# H_BRIDGE.net
KiCad netlist of a schematic drawn in Altium Designer
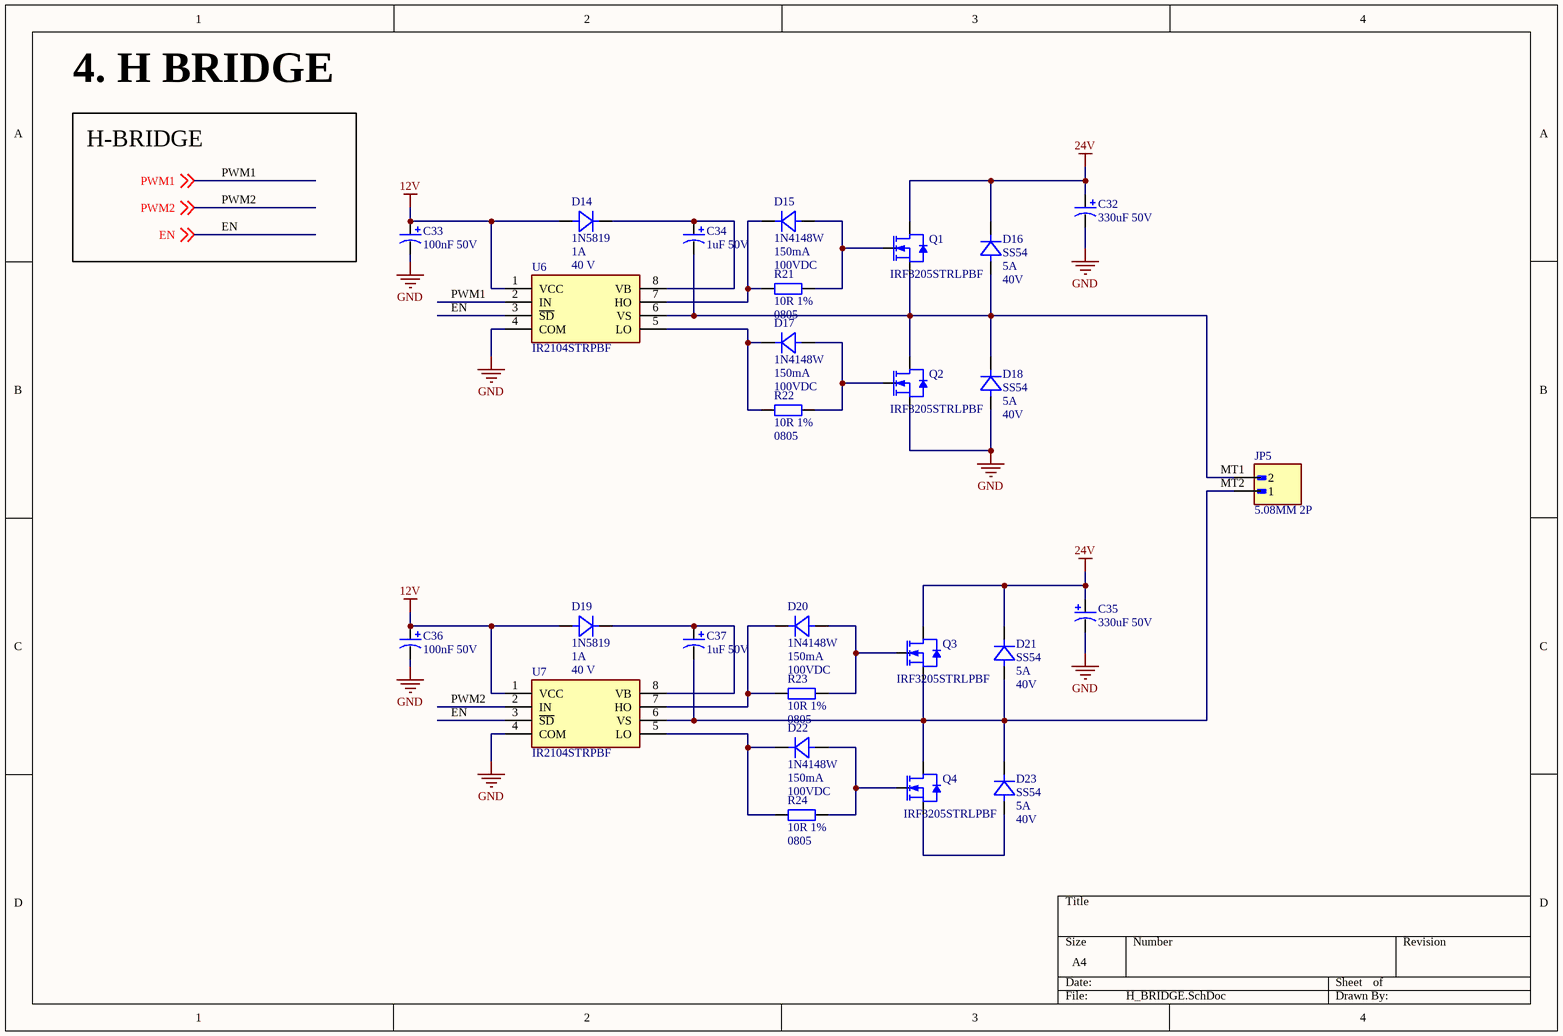
[diagram p0: H_BRIDGE.SchDoc]

(export (version "E")
  (design (tool "Eeschema 10.0.6"))
  (components
    (comp (ref "C32")
      (value "330uF 50V")
      (footprint "CAP-ALU-SMD-G-NEW")
      (description "330uF 50V 170mA@120Hz ±20% SMD,D10xL10.2mm Aluminum Electrolytic Capacitors - SMD ROHS")
      (fields
        (field (name "MANUFACTURER") "KNSCHA")
        (field (name "MANUFACTURE PART NUMBER") "RVT330UF50V167RV085")
      )
      (libsource (lib "Capacitors") (part "C_ALU_330uF_50V_G"))
    )
    (comp (ref "C33")
      (value "100nF 50V")
      (footprint "CAP-ALU-SMD-B -NEW")
      (description "100nF 50V ±20% SMD,D4xL5.4mm Aluminum Electrolytic Capacitors - SMD ROHS")
      (fields
        (field (name "MANUFACTURER") "Changzhou Huawei Elec")
        (field (name "MANUFACTURE PART NUMBER") "VT1H0R1MB054000CE0")
      )
      (libsource (lib "Capacitors") (part "C_ALU_100nF_50V_B"))
    )
    (comp (ref "C34")
      (value "1uF 50V")
      (footprint "CAP-ALU-SMD-B -NEW")
      (description "1uF 50V 7mA@120Hz ±20% SMD,D4xL5.4mm Aluminum Electrolytic Capacitors - SMD ROHS")
      (fields (field (name "MANUFACTURER") "KNSCHA") (field (name "MANUFACTURE PART NUMBER") "RST1UF50V017"))
      (libsource (lib "Capacitors") (part "C_ALU_1uF_50V_B"))
    )
    (comp (ref "C35")
      (value "330uF 50V")
      (footprint "CAP-ALU-SMD-G-NEW")
      (description "330uF 50V 170mA@120Hz ±20% SMD,D10xL10.2mm Aluminum Electrolytic Capacitors - SMD ROHS")
      (fields
        (field (name "MANUFACTURER") "KNSCHA")
        (field (name "MANUFACTURE PART NUMBER") "RVT330UF50V167RV085")
      )
      (libsource (lib "") (part "C_ALU_330uF_50V_G_1"))
    )
    (comp (ref "C36")
      (value "100nF 50V")
      (footprint "CAP-ALU-SMD-B -NEW")
      (description "100nF 50V ±20% SMD,D4xL5.4mm Aluminum Electrolytic Capacitors - SMD ROHS")
      (fields
        (field (name "MANUFACTURER") "Changzhou Huawei Elec")
        (field (name "MANUFACTURE PART NUMBER") "VT1H0R1MB054000CE0")
      )
      (libsource (lib "Capacitors") (part "C_ALU_100nF_50V_B"))
    )
    (comp (ref "C37")
      (value "1uF 50V")
      (footprint "CAP-ALU-SMD-B -NEW")
      (description "1uF 50V 7mA@120Hz ±20% SMD,D4xL5.4mm Aluminum Electrolytic Capacitors - SMD ROHS")
      (fields (field (name "MANUFACTURER") "KNSCHA") (field (name "MANUFACTURE PART NUMBER") "RST1UF50V017"))
      (libsource (lib "Capacitors") (part "C_ALU_1uF_50V_B"))
    )
    (comp (ref "D14")
      (value "1N5819")
      (footprint "DIO-SMD-123")
      (description "Diode 40 V 1A Surface Mount SOD-123")
      (fields
        (field (name "MANUFACTURER") "Diodes Incorporated")
        (field (name "MANUFACTURE PART NUMBER") "1N5819HW-7-F")
        (field (name "CURRENT - AVERAGE RECTIFIED (IO)") "1A")
        (field (name "VOLTAGE - DC REVERSE (VR) (MAX)") "40 V")
      )
      (libsource (lib "Diode") (part "1N5819"))
    )
    (comp (ref "D15")
      (value "1N4148W")
      (footprint "DIO-SMD-123")
      (description "Diode 100 V 150mA Surface Mount SOD-123")
      (fields
        (field (name "MANUFACTURER") "Micro Commercial Co")
        (field (name "MANUFACTURE PART NUMBER") "1N4148W-TP")
        (field (name "CURRENT") "150mA")
        (field (name "DC VOLTAGE") "100VDC")
      )
      (libsource (lib "Diode") (part "1N4148W-TP"))
    )
    (comp (ref "D16")
      (value "SS54")
      (footprint "SMA")
      (description "DIODE SCHOTTKY 40V 5A SMA")
      (fields
        (field (name "MANUFACTURER") "EVVO")
        (field (name "CURRENT") "5A")
        (field (name "DC VOLTAGE") "40V")
      )
      (libsource (lib "Diode") (part "SS54"))
    )
    (comp (ref "D17")
      (value "1N4148W")
      (footprint "DIO-SMD-123")
      (description "Diode 100 V 150mA Surface Mount SOD-123")
      (fields
        (field (name "MANUFACTURER") "Micro Commercial Co")
        (field (name "MANUFACTURE PART NUMBER") "1N4148W-TP")
        (field (name "CURRENT") "150mA")
        (field (name "DC VOLTAGE") "100VDC")
      )
      (libsource (lib "Diode") (part "1N4148W-TP"))
    )
    (comp (ref "D18")
      (value "SS54")
      (footprint "SMA")
      (description "DIODE SCHOTTKY 40V 5A SMA")
      (fields
        (field (name "MANUFACTURER") "EVVO")
        (field (name "CURRENT") "5A")
        (field (name "DC VOLTAGE") "40V")
      )
      (libsource (lib "Diode") (part "SS54"))
    )
    (comp (ref "D19")
      (value "1N5819")
      (footprint "DIO-SMD-123")
      (description "Diode 40 V 1A Surface Mount SOD-123")
      (fields
        (field (name "MANUFACTURER") "Diodes Incorporated")
        (field (name "MANUFACTURE PART NUMBER") "1N5819HW-7-F")
        (field (name "CURRENT - AVERAGE RECTIFIED (IO)") "1A")
        (field (name "VOLTAGE - DC REVERSE (VR) (MAX)") "40 V")
      )
      (libsource (lib "Diode") (part "1N5819"))
    )
    (comp (ref "D20")
      (value "1N4148W")
      (footprint "DIO-SMD-123")
      (description "Diode 100 V 150mA Surface Mount SOD-123")
      (fields
        (field (name "MANUFACTURER") "Micro Commercial Co")
        (field (name "MANUFACTURE PART NUMBER") "1N4148W-TP")
        (field (name "CURRENT") "150mA")
        (field (name "DC VOLTAGE") "100VDC")
      )
      (libsource (lib "Diode") (part "1N4148W-TP"))
    )
    (comp (ref "D21")
      (value "SS54")
      (footprint "SMA")
      (description "DIODE SCHOTTKY 40V 5A SMA")
      (fields
        (field (name "MANUFACTURER") "EVVO")
        (field (name "CURRENT") "5A")
        (field (name "DC VOLTAGE") "40V")
      )
      (libsource (lib "Diode") (part "SS54"))
    )
    (comp (ref "D22")
      (value "1N4148W")
      (footprint "DIO-SMD-123")
      (description "Diode 100 V 150mA Surface Mount SOD-123")
      (fields
        (field (name "MANUFACTURER") "Micro Commercial Co")
        (field (name "MANUFACTURE PART NUMBER") "1N4148W-TP")
        (field (name "CURRENT") "150mA")
        (field (name "DC VOLTAGE") "100VDC")
      )
      (libsource (lib "Diode") (part "1N4148W-TP"))
    )
    (comp (ref "D23")
      (value "SS54")
      (footprint "SMA")
      (description "DIODE SCHOTTKY 40V 5A SMA")
      (fields
        (field (name "MANUFACTURER") "EVVO")
        (field (name "CURRENT") "5A")
        (field (name "DC VOLTAGE") "40V")
      )
      (libsource (lib "Diode") (part "SS54"))
    )
    (comp (ref "JP5")
      (value "5.08MM 2P")
      (footprint "5.08MM 2P")
      (fields
        (field (name "MANUFACTURER") "Phoenix Contact")
        (field (name "MANUFACTURE PART NUMBER") "1759017")
      )
      (libsource (lib "Connectors") (part "TERMINAL_5.08MM_2P"))
    )
    (comp (ref "Q1")
      (value "IRF3205STRLPBF")
      (footprint "TO263-3")
      (description "N-Channel 55 V 110A (Tc) 200W (Tc) Surface Mount D2PAK")
      (fields (field (name "MANUFACTURER") "Infineon Technologies"))
      (libsource (lib "Trans_Fets") (part "IRF3205STRLPBF"))
    )
    (comp (ref "Q2")
      (value "IRF3205STRLPBF")
      (footprint "TO263-3")
      (description "N-Channel 55 V 110A (Tc) 200W (Tc) Surface Mount D2PAK")
      (fields (field (name "MANUFACTURER") "Infineon Technologies"))
      (libsource (lib "Trans_Fets") (part "IRF3205STRLPBF"))
    )
    (comp (ref "Q3")
      (value "IRF3205STRLPBF")
      (footprint "TO263-3")
      (description "N-Channel 55 V 110A (Tc) 200W (Tc) Surface Mount D2PAK")
      (fields (field (name "MANUFACTURER") "Infineon Technologies"))
      (libsource (lib "Trans_Fets") (part "IRF3205STRLPBF"))
    )
    (comp (ref "Q4")
      (value "IRF3205STRLPBF")
      (footprint "TO263-3")
      (description "N-Channel 55 V 110A (Tc) 200W (Tc) Surface Mount D2PAK")
      (fields (field (name "MANUFACTURER") "Infineon Technologies"))
      (libsource (lib "Trans_Fets") (part "IRF3205STRLPBF"))
    )
    (comp (ref "R21")
      (value "10R 1%")
      (footprint "RES_SMD_0805")
      (description "10 Ohms ±1% 0.125W, 1/8W Chip Resistor 0805 (2012 Metric) Moisture Resistant Thick Film")
      (fields
        (field (name "MANUFACTURER") "YAGEO")
        (field (name "MANUFACTURE PART NUMBER") "RC0805FR-0710RL")
        (field (name "SIZE") "0805")
      )
      (libsource (lib "Resistors") (part "R0805_10R"))
    )
    (comp (ref "R22")
      (value "10R 1%")
      (footprint "RES_SMD_0805")
      (description "10 Ohms ±1% 0.125W, 1/8W Chip Resistor 0805 (2012 Metric) Moisture Resistant Thick Film")
      (fields
        (field (name "MANUFACTURER") "YAGEO")
        (field (name "MANUFACTURE PART NUMBER") "RC0805FR-0710RL")
        (field (name "SIZE") "0805")
      )
      (libsource (lib "Resistors") (part "R0805_10R"))
    )
    (comp (ref "R23")
      (value "10R 1%")
      (footprint "RES_SMD_0805")
      (description "10 Ohms ±1% 0.125W, 1/8W Chip Resistor 0805 (2012 Metric) Moisture Resistant Thick Film")
      (fields
        (field (name "MANUFACTURER") "YAGEO")
        (field (name "MANUFACTURE PART NUMBER") "RC0805FR-0710RL")
        (field (name "SIZE") "0805")
      )
      (libsource (lib "Resistors") (part "R0805_10R"))
    )
    (comp (ref "R24")
      (value "10R 1%")
      (footprint "RES_SMD_0805")
      (description "10 Ohms ±1% 0.125W, 1/8W Chip Resistor 0805 (2012 Metric) Moisture Resistant Thick Film")
      (fields
        (field (name "MANUFACTURER") "YAGEO")
        (field (name "MANUFACTURE PART NUMBER") "RC0805FR-0710RL")
        (field (name "SIZE") "0805")
      )
      (libsource (lib "Resistors") (part "R0805_10R"))
    )
    (comp (ref "U6")
      (value "IR2104STRPBF")
      (footprint "SOIC-8")
      (description "Half Bridge 2 210mA 100ns 50ns 10V~20V 360mA SOIC-8 Gate Drivers ROHS")
      (fields (field (name "MANUFACTURER") "Infineon Technologies"))
      (libsource (lib "ICs") (part "IR2104STRPBF"))
    )
    (comp (ref "U7")
      (value "IR2104STRPBF")
      (footprint "SOIC-8")
      (description "Half Bridge 2 210mA 100ns 50ns 10V~20V 360mA SOIC-8 Gate Drivers ROHS")
      (fields (field (name "MANUFACTURER") "Infineon Technologies"))
      (libsource (lib "ICs") (part "IR2104STRPBF"))
    )
  )
  (nets
    (net (code "1") (name "/MT1") (class "Default")
      (node (ref "C34") (pin "2") (pinfunction "2_2") (pintype "passive"))
      (node (ref "D16") (pin "A") (pinfunction "A_A") (pintype "passive"))
      (node (ref "D18") (pin "C") (pinfunction "C_C") (pintype "passive"))
      (node (ref "JP5") (pin "2") (pinfunction "2_2") (pintype "passive"))
      (node (ref "Q1") (pin "3") (pinfunction "S_3") (pintype "passive"))
      (node (ref "Q2") (pin "4") (pinfunction "D_4") (pintype "passive"))
      (node (ref "U6") (pin "6") (pinfunction "VS_6") (pintype "passive"))
    )
    (net (code "2") (name "/MT2") (class "Default")
      (node (ref "C37") (pin "2") (pinfunction "2_2") (pintype "passive"))
      (node (ref "D21") (pin "A") (pinfunction "A_A") (pintype "passive"))
      (node (ref "D23") (pin "C") (pinfunction "C_C") (pintype "passive"))
      (node (ref "JP5") (pin "1") (pinfunction "1_1") (pintype "passive"))
      (node (ref "Q3") (pin "3") (pinfunction "S_3") (pintype "passive"))
      (node (ref "Q4") (pin "4") (pinfunction "D_4") (pintype "passive"))
      (node (ref "U7") (pin "6") (pinfunction "VS_6") (pintype "passive"))
    )
    (net (code "3") (name "12V") (class "Default")
      (node (ref "C33") (pin "1") (pinfunction "1_1") (pintype "passive"))
      (node (ref "C36") (pin "1") (pinfunction "1_1") (pintype "passive"))
      (node (ref "D14") (pin "A") (pinfunction "A_A") (pintype "passive"))
      (node (ref "D19") (pin "A") (pinfunction "A_A") (pintype "passive"))
      (node (ref "U6") (pin "1") (pinfunction "VCC_1") (pintype "passive"))
      (node (ref "U7") (pin "1") (pinfunction "VCC_1") (pintype "passive"))
    )
    (net (code "4") (name "24V") (class "Default")
      (node (ref "C32") (pin "1") (pinfunction "1_1") (pintype "passive"))
      (node (ref "C35") (pin "1") (pinfunction "1_1") (pintype "passive"))
      (node (ref "D16") (pin "C") (pinfunction "C_C") (pintype "passive"))
      (node (ref "D21") (pin "C") (pinfunction "C_C") (pintype "passive"))
      (node (ref "Q1") (pin "4") (pinfunction "D_4") (pintype "passive"))
      (node (ref "Q3") (pin "4") (pinfunction "D_4") (pintype "passive"))
    )
    (net (code "5") (name "EN") (class "Default")
      (node (ref "U6") (pin "3") (pinfunction "~{SD}_3") (pintype "passive"))
      (node (ref "U7") (pin "3") (pinfunction "~{SD}_3") (pintype "passive"))
    )
    (net (code "6") (name "GND") (class "Default")
      (node (ref "C32") (pin "2") (pinfunction "2_2") (pintype "passive"))
      (node (ref "C33") (pin "2") (pinfunction "2_2") (pintype "passive"))
      (node (ref "C35") (pin "2") (pinfunction "2_2") (pintype "passive"))
      (node (ref "C36") (pin "2") (pinfunction "2_2") (pintype "passive"))
      (node (ref "D18") (pin "A") (pinfunction "A_A") (pintype "passive"))
      (node (ref "Q2") (pin "3") (pinfunction "S_3") (pintype "passive"))
      (node (ref "U6") (pin "4") (pinfunction "COM_4") (pintype "passive"))
      (node (ref "U7") (pin "4") (pinfunction "COM_4") (pintype "passive"))
    )
    (net (code "7") (name "Net-(Q1-G)") (class "Default")
      (node (ref "D15") (pin "A") (pinfunction "A_A") (pintype "passive"))
      (node (ref "Q1") (pin "1") (pinfunction "G_1") (pintype "passive"))
      (node (ref "R21") (pin "2") (pinfunction "2_2") (pintype "passive"))
    )
    (net (code "8") (name "Net-(Q2-G)") (class "Default")
      (node (ref "D17") (pin "A") (pinfunction "A_A") (pintype "passive"))
      (node (ref "Q2") (pin "1") (pinfunction "G_1") (pintype "passive"))
      (node (ref "R22") (pin "2") (pinfunction "2_2") (pintype "passive"))
    )
    (net (code "9") (name "Net-(Q3-G)") (class "Default")
      (node (ref "D20") (pin "A") (pinfunction "A_A") (pintype "passive"))
      (node (ref "Q3") (pin "1") (pinfunction "G_1") (pintype "passive"))
      (node (ref "R23") (pin "2") (pinfunction "2_2") (pintype "passive"))
    )
    (net (code "10") (name "Net-(Q4-G)") (class "Default")
      (node (ref "D22") (pin "A") (pinfunction "A_A") (pintype "passive"))
      (node (ref "Q4") (pin "1") (pinfunction "G_1") (pintype "passive"))
      (node (ref "R24") (pin "2") (pinfunction "2_2") (pintype "passive"))
    )
    (net (code "11") (name "Net-(Q4-S)") (class "Default")
      (node (ref "D23") (pin "A") (pinfunction "A_A") (pintype "passive"))
      (node (ref "Q4") (pin "3") (pinfunction "S_3") (pintype "passive"))
    )
    (net (code "12") (name "Net-(U6-HO)") (class "Default")
      (node (ref "D15") (pin "C") (pinfunction "C_C") (pintype "passive"))
      (node (ref "R21") (pin "1") (pinfunction "1_1") (pintype "passive"))
      (node (ref "U6") (pin "7") (pinfunction "HO_7") (pintype "passive"))
    )
    (net (code "13") (name "Net-(U6-LO)") (class "Default")
      (node (ref "D17") (pin "C") (pinfunction "C_C") (pintype "passive"))
      (node (ref "R22") (pin "1") (pinfunction "1_1") (pintype "passive"))
      (node (ref "U6") (pin "5") (pinfunction "LO_5") (pintype "passive"))
    )
    (net (code "14") (name "Net-(U6-VB)") (class "Default")
      (node (ref "C34") (pin "1") (pinfunction "1_1") (pintype "passive"))
      (node (ref "D14") (pin "C") (pinfunction "C_C") (pintype "passive"))
      (node (ref "U6") (pin "8") (pinfunction "VB_8") (pintype "passive"))
    )
    (net (code "15") (name "Net-(U7-HO)") (class "Default")
      (node (ref "D20") (pin "C") (pinfunction "C_C") (pintype "passive"))
      (node (ref "R23") (pin "1") (pinfunction "1_1") (pintype "passive"))
      (node (ref "U7") (pin "7") (pinfunction "HO_7") (pintype "passive"))
    )
    (net (code "16") (name "Net-(U7-LO)") (class "Default")
      (node (ref "D22") (pin "C") (pinfunction "C_C") (pintype "passive"))
      (node (ref "R24") (pin "1") (pinfunction "1_1") (pintype "passive"))
      (node (ref "U7") (pin "5") (pinfunction "LO_5") (pintype "passive"))
    )
    (net (code "17") (name "Net-(U7-VB)") (class "Default")
      (node (ref "C37") (pin "1") (pinfunction "1_1") (pintype "passive"))
      (node (ref "D19") (pin "C") (pinfunction "C_C") (pintype "passive"))
      (node (ref "U7") (pin "8") (pinfunction "VB_8") (pintype "passive"))
    )
    (net (code "18") (name "PWM1") (class "Default")
      (node (ref "U6") (pin "2") (pinfunction "IN_2") (pintype "passive"))
    )
    (net (code "19") (name "PWM2") (class "Default")
      (node (ref "U7") (pin "2") (pinfunction "IN_2") (pintype "passive"))
    )
  )
)
